# SCH_GroeiAcademie-v0_10_00_2026-07-24.net
KiCad netlist of a schematic drawn in EasyEDA
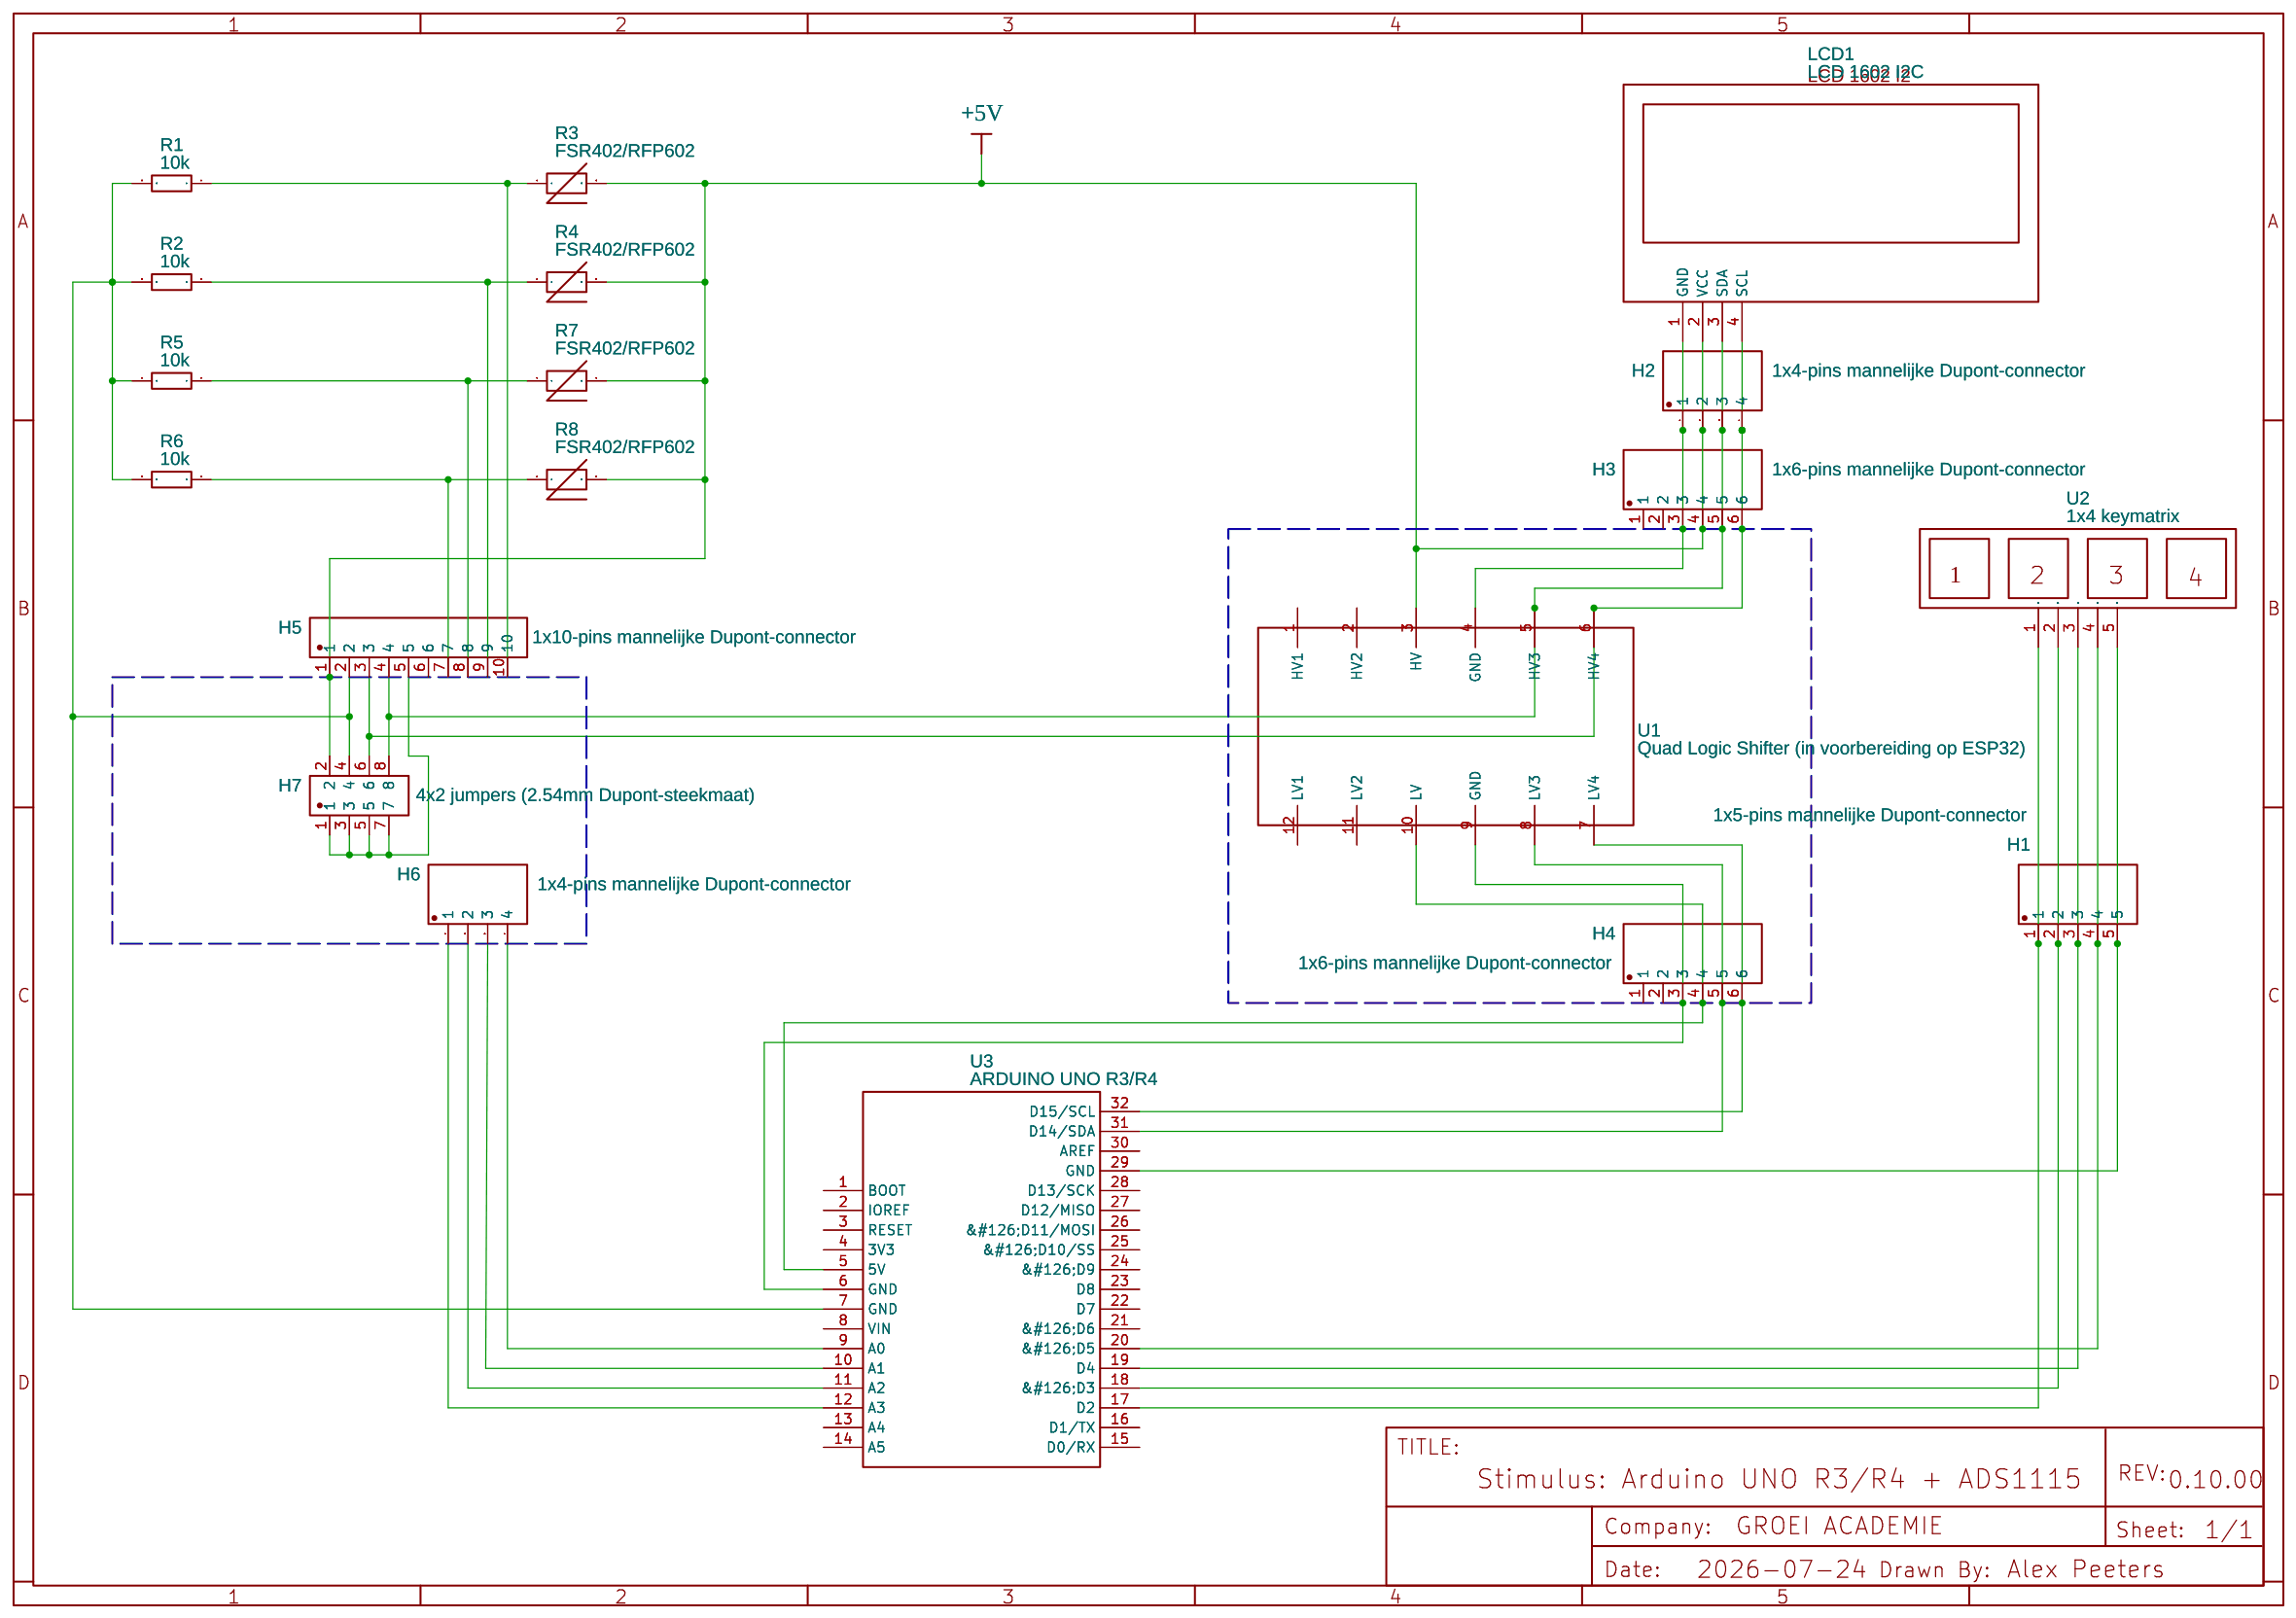
[diagram p0: schematic sheet]

(export (version "E")
  (design (tool "Eeschema 10.0.6"))
  (components
    (comp (ref "H1")
      (value "1x5-pins mannelijke Dupont-connector")
      (fields (field (name "Manufacturer Part") "B-2100S05P-A110") (field (name "Manufacturer") "Ckmtw(灿科盟)"))
      (libsource (lib "") (part "210S-1*5P L=11.6MMGold-plated black"))
    )
    (comp (ref "H2")
      (value "1x4-pins mannelijke Dupont-connector")
      (fields (field (name "Manufacturer Part") "B-2100S04P-A110") (field (name "Manufacturer") "Ckmtw(灿科盟)"))
      (libsource (lib "") (part "Header-Male-2.54_1x4"))
    )
    (comp (ref "H3")
      (value "1x6-pins mannelijke Dupont-connector")
      (fields (field (name "Manufacturer Part") "B-2100S06P-A110") (field (name "Manufacturer") "Ckmtw(灿科盟)"))
      (libsource (lib "") (part "210S-1*6P L=11.6MMGold-plated black"))
    )
    (comp (ref "H4")
      (value "1x6-pins mannelijke Dupont-connector")
      (fields (field (name "Manufacturer Part") "B-2100S06P-A110") (field (name "Manufacturer") "Ckmtw(灿科盟)"))
      (libsource (lib "") (part "210S-1*6P L=11.6MMGold-plated black"))
    )
    (comp (ref "H5")
      (value "1x10-pins mannelijke Dupont-connector")
      (fields (field (name "Manufacturer Part") "2.54-1*10") (field (name "Manufacturer") "ZHOURI(洲日)"))
      (libsource (lib "") (part "2.54-1*10"))
    )
    (comp (ref "H6")
      (value "1x4-pins mannelijke Dupont-connector")
      (fields (field (name "Manufacturer Part") "B-2100S04P-A110") (field (name "Manufacturer") "Ckmtw(灿科盟)"))
      (libsource (lib "") (part "Header-Male-2.54_1x4"))
    )
    (comp (ref "H7")
      (value "4x2 jumpers (2.54mm Dupont-steekmaat)")
      (fields (field (name "Manufacturer Part") "2.54-2*4P立贴针") (field (name "Manufacturer") "BOOMELE(博穆精密)"))
      (libsource (lib "") (part "2.54-2*4P立贴针"))
    )
    (comp (ref "LCD1") (value "LCD 1602 I2C") (libsource (lib "") (part "I2CLCD16X2_N")))
    (comp (ref "R1")
      (value "10k")
      (fields (field (name "Manufacturer") "Made in China"))
      (libsource (lib "") (part "330Ω (331) ±5%"))
    )
    (comp (ref "R2")
      (value "10k")
      (fields (field (name "Manufacturer") "Made in China"))
      (libsource (lib "") (part "330Ω (331) ±5%"))
    )
    (comp (ref "R3") (value "FSR402/RFP602") (libsource (lib "") (part "FSR402-OPCION1")))
    (comp (ref "R4") (value "FSR402/RFP602") (libsource (lib "") (part "FSR402-OPCION1")))
    (comp (ref "R5")
      (value "10k")
      (fields (field (name "Manufacturer") "Made in China"))
      (libsource (lib "") (part "330Ω (331) ±5%"))
    )
    (comp (ref "R6")
      (value "10k")
      (fields (field (name "Manufacturer") "Made in China"))
      (libsource (lib "") (part "330Ω (331) ±5%"))
    )
    (comp (ref "R7") (value "FSR402/RFP602") (libsource (lib "") (part "FSR402-OPCION1")))
    (comp (ref "R8") (value "FSR402/RFP602") (libsource (lib "") (part "FSR402-OPCION1")))
    (comp (ref "U1")
      (value "Quad Logic Shifter (in voorbereiding op ESP32)")
      (libsource (lib "") (part "Quad Logic Shifter"))
    )
    (comp (ref "U2") (value "1x4 keymatrix") (libsource (lib "") (part "Клавиатура 4*4")))
    (comp (ref "U3") (value "ARDUINO UNO R3/R4") (libsource (lib "") (part "ARDUINO UNO R4 MINIMA")))
  )
  (nets
    (net (code "1") (name "+5V") (class "Default")
      (node (ref "H2") (pin "2") (pinfunction "2_2") (pintype "unspecified"))
      (node (ref "H3") (pin "4") (pinfunction "4_4") (pintype "unspecified"))
      (node (ref "H5") (pin "1") (pinfunction "1_1") (pintype "unspecified"))
      (node (ref "H7") (pin "2") (pinfunction "2_2") (pintype "unspecified"))
      (node (ref "LCD1") (pin "2") (pinfunction "VCC_2") (pintype "unspecified"))
      (node (ref "R3") (pin "2") (pinfunction "2_2") (pintype "unspecified"))
      (node (ref "R4") (pin "2") (pinfunction "2_2") (pintype "unspecified"))
      (node (ref "R7") (pin "2") (pinfunction "2_2") (pintype "unspecified"))
      (node (ref "R8") (pin "2") (pinfunction "2_2") (pintype "unspecified"))
      (node (ref "U1") (pin "3") (pinfunction "HV_3") (pintype "unspecified"))
    )
    (net (code "2") (name "Net-(H4-Pad3)") (class "Default")
      (node (ref "H4") (pin "3") (pinfunction "3_3") (pintype "unspecified"))
      (node (ref "U1") (pin "9") (pinfunction "GND_9") (pintype "unspecified"))
      (node (ref "U3") (pin "6") (pinfunction "GND_6") (pintype "unspecified"))
    )
    (net (code "3") (name "Net-(H5-Pad2)") (class "Default")
      (node (ref "H5") (pin "2") (pinfunction "2_2") (pintype "unspecified"))
      (node (ref "H7") (pin "4") (pinfunction "4_4") (pintype "unspecified"))
      (node (ref "R1") (pin "2") (pinfunction "2_2") (pintype "unspecified"))
      (node (ref "R2") (pin "2") (pinfunction "2_2") (pintype "unspecified"))
      (node (ref "R5") (pin "2") (pinfunction "2_2") (pintype "unspecified"))
      (node (ref "R6") (pin "2") (pinfunction "2_2") (pintype "unspecified"))
      (node (ref "U3") (pin "7") (pinfunction "GND_7") (pintype "unspecified"))
    )
    (net (code "4") (name "Net-(H5-Pad5)") (class "Default")
      (node (ref "H5") (pin "5") (pinfunction "5_5") (pintype "unspecified"))
      (node (ref "H7") (pin "1") (pinfunction "1_1") (pintype "unspecified"))
      (node (ref "H7") (pin "3") (pinfunction "3_3") (pintype "unspecified"))
      (node (ref "H7") (pin "5") (pinfunction "5_5") (pintype "unspecified"))
      (node (ref "H7") (pin "7") (pinfunction "7_7") (pintype "unspecified"))
    )
    (net (code "5") (name "Net-(H5-Pad7)") (class "Default")
      (node (ref "H5") (pin "7") (pinfunction "7_7") (pintype "unspecified"))
      (node (ref "R6") (pin "1") (pinfunction "1_1") (pintype "unspecified"))
      (node (ref "R8") (pin "1") (pinfunction "1_1") (pintype "unspecified"))
    )
    (net (code "6") (name "Net-(H5-Pad8)") (class "Default")
      (node (ref "H5") (pin "8") (pinfunction "8_8") (pintype "unspecified"))
      (node (ref "R5") (pin "1") (pinfunction "1_1") (pintype "unspecified"))
      (node (ref "R7") (pin "1") (pinfunction "1_1") (pintype "unspecified"))
    )
    (net (code "7") (name "Net-(H5-Pad9)") (class "Default")
      (node (ref "H5") (pin "9") (pinfunction "9_9") (pintype "unspecified"))
      (node (ref "R2") (pin "1") (pinfunction "1_1") (pintype "unspecified"))
      (node (ref "R4") (pin "1") (pinfunction "1_1") (pintype "unspecified"))
    )
    (net (code "8") (name "Net-(H5-Pad10)") (class "Default")
      (node (ref "H5") (pin "10") (pinfunction "10_10") (pintype "unspecified"))
      (node (ref "R1") (pin "1") (pinfunction "1_1") (pintype "unspecified"))
      (node (ref "R3") (pin "1") (pinfunction "1_1") (pintype "unspecified"))
    )
    (net (code "9") (name "Net-(LCD1-GND)") (class "Default")
      (node (ref "H2") (pin "1") (pinfunction "1_1") (pintype "unspecified"))
      (node (ref "H3") (pin "3") (pinfunction "3_3") (pintype "unspecified"))
      (node (ref "LCD1") (pin "1") (pinfunction "GND_1") (pintype "unspecified"))
      (node (ref "U1") (pin "4") (pinfunction "GND_4") (pintype "unspecified"))
    )
    (net (code "10") (name "Net-(LCD1-SCL)") (class "Default")
      (node (ref "H2") (pin "4") (pinfunction "4_4") (pintype "unspecified"))
      (node (ref "H3") (pin "6") (pinfunction "6_6") (pintype "unspecified"))
      (node (ref "H5") (pin "3") (pinfunction "3_3") (pintype "unspecified"))
      (node (ref "H7") (pin "6") (pinfunction "6_6") (pintype "unspecified"))
      (node (ref "LCD1") (pin "4") (pinfunction "SCL_4") (pintype "unspecified"))
      (node (ref "U1") (pin "6") (pinfunction "HV4_6") (pintype "unspecified"))
    )
    (net (code "11") (name "Net-(LCD1-SDA)") (class "Default")
      (node (ref "H2") (pin "3") (pinfunction "3_3") (pintype "unspecified"))
      (node (ref "H3") (pin "5") (pinfunction "5_5") (pintype "unspecified"))
      (node (ref "H5") (pin "4") (pinfunction "4_4") (pintype "unspecified"))
      (node (ref "H7") (pin "8") (pinfunction "8_8") (pintype "unspecified"))
      (node (ref "LCD1") (pin "3") (pinfunction "SDA_3") (pintype "unspecified"))
      (node (ref "U1") (pin "5") (pinfunction "HV3_5") (pintype "unspecified"))
    )
    (net (code "12") (name "Net-(U1-LV)") (class "Default")
      (node (ref "H4") (pin "4") (pinfunction "4_4") (pintype "unspecified"))
      (node (ref "U1") (pin "10") (pinfunction "LV_10") (pintype "unspecified"))
      (node (ref "U3") (pin "5") (pinfunction "5V_5") (pintype "unspecified"))
    )
    (net (code "13") (name "Net-(U1-LV3)") (class "Default")
      (node (ref "H4") (pin "5") (pinfunction "5_5") (pintype "unspecified"))
      (node (ref "U1") (pin "8") (pinfunction "LV3_8") (pintype "unspecified"))
      (node (ref "U3") (pin "31") (pinfunction "D14/SDA_31") (pintype "unspecified"))
    )
    (net (code "14") (name "Net-(U1-LV4)") (class "Default")
      (node (ref "H4") (pin "6") (pinfunction "6_6") (pintype "unspecified"))
      (node (ref "U1") (pin "7") (pinfunction "LV4_7") (pintype "unspecified"))
      (node (ref "U3") (pin "32") (pinfunction "D15/SCL_32") (pintype "unspecified"))
    )
    (net (code "15") (name "Net-(U2-C1)") (class "Default")
      (node (ref "H1") (pin "1") (pinfunction "1_1") (pintype "unspecified"))
      (node (ref "U2") (pin "1") (pinfunction "C1_1") (pintype "unspecified"))
      (node (ref "U3") (pin "17") (pinfunction "D2_17") (pintype "unspecified"))
    )
    (net (code "16") (name "Net-(U2-C2)") (class "Default")
      (node (ref "H1") (pin "2") (pinfunction "2_2") (pintype "unspecified"))
      (node (ref "U2") (pin "2") (pinfunction "C2_2") (pintype "unspecified"))
      (node (ref "U3") (pin "18") (pinfunction "&#126;D3_18") (pintype "unspecified"))
    )
    (net (code "17") (name "Net-(U2-C3)") (class "Default")
      (node (ref "H1") (pin "3") (pinfunction "3_3") (pintype "unspecified"))
      (node (ref "U2") (pin "3") (pinfunction "C3_3") (pintype "unspecified"))
      (node (ref "U3") (pin "19") (pinfunction "D4_19") (pintype "unspecified"))
    )
    (net (code "18") (name "Net-(U2-R1)") (class "Default")
      (node (ref "H1") (pin "4") (pinfunction "4_4") (pintype "unspecified"))
      (node (ref "U2") (pin "4") (pinfunction "R1_4") (pintype "unspecified"))
      (node (ref "U3") (pin "20") (pinfunction "&#126;D5_20") (pintype "unspecified"))
    )
    (net (code "19") (name "Net-(U2-R2)") (class "Default")
      (node (ref "H1") (pin "5") (pinfunction "5_5") (pintype "unspecified"))
      (node (ref "U2") (pin "5") (pinfunction "R2_5") (pintype "unspecified"))
      (node (ref "U3") (pin "29") (pinfunction "GND_29") (pintype "unspecified"))
    )
    (net (code "20") (name "Net-(U3-A0)") (class "Default")
      (node (ref "H6") (pin "4") (pinfunction "4_4") (pintype "unspecified"))
      (node (ref "U3") (pin "9") (pinfunction "A0_9") (pintype "unspecified"))
    )
    (net (code "21") (name "Net-(U3-A1)") (class "Default")
      (node (ref "H6") (pin "3") (pinfunction "3_3") (pintype "unspecified"))
      (node (ref "U3") (pin "10") (pinfunction "A1_10") (pintype "unspecified"))
    )
    (net (code "22") (name "Net-(U3-A2)") (class "Default")
      (node (ref "H6") (pin "2") (pinfunction "2_2") (pintype "unspecified"))
      (node (ref "U3") (pin "11") (pinfunction "A2_11") (pintype "unspecified"))
    )
    (net (code "23") (name "Net-(U3-A3)") (class "Default")
      (node (ref "H6") (pin "1") (pinfunction "1_1") (pintype "unspecified"))
      (node (ref "U3") (pin "12") (pinfunction "A3_12") (pintype "unspecified"))
    )
    (net (code "24") (name "unconnected-(H3-Pad1)") (class "Default")
      (node (ref "H3") (pin "1") (pinfunction "1_1") (pintype "unspecified"))
    )
    (net (code "25") (name "unconnected-(H3-Pad2)") (class "Default")
      (node (ref "H3") (pin "2") (pinfunction "2_2") (pintype "unspecified"))
    )
    (net (code "26") (name "unconnected-(H4-Pad1)") (class "Default")
      (node (ref "H4") (pin "1") (pinfunction "1_1") (pintype "unspecified"))
    )
    (net (code "27") (name "unconnected-(H4-Pad2)") (class "Default")
      (node (ref "H4") (pin "2") (pinfunction "2_2") (pintype "unspecified"))
    )
    (net (code "28") (name "unconnected-(H5-Pad6)") (class "Default")
      (node (ref "H5") (pin "6") (pinfunction "6_6") (pintype "unspecified"))
    )
    (net (code "29") (name "unconnected-(U1-HV1-Pad1)") (class "Default")
      (node (ref "U1") (pin "1") (pinfunction "HV1_1") (pintype "unspecified"))
    )
    (net (code "30") (name "unconnected-(U1-HV2-Pad2)") (class "Default")
      (node (ref "U1") (pin "2") (pinfunction "HV2_2") (pintype "unspecified"))
    )
    (net (code "31") (name "unconnected-(U1-LV1-Pad12)") (class "Default")
      (node (ref "U1") (pin "12") (pinfunction "LV1_12") (pintype "unspecified"))
    )
    (net (code "32") (name "unconnected-(U1-LV2-Pad11)") (class "Default")
      (node (ref "U1") (pin "11") (pinfunction "LV2_11") (pintype "unspecified"))
    )
    (net (code "33") (name "unconnected-(U3-&#126;D6-Pad21)") (class "Default")
      (node (ref "U3") (pin "21") (pinfunction "&#126;D6_21") (pintype "unspecified"))
    )
    (net (code "34") (name "unconnected-(U3-&#126;D9-Pad24)") (class "Default")
      (node (ref "U3") (pin "24") (pinfunction "&#126;D9_24") (pintype "unspecified"))
    )
    (net (code "35") (name "unconnected-(U3-&#126;D10{slash}SS-Pad25)") (class "Default")
      (node (ref "U3") (pin "25") (pinfunction "&#126;D10/SS_25") (pintype "unspecified"))
    )
    (net (code "36") (name "unconnected-(U3-&#126;D11{slash}MOSI-Pad26)") (class "Default")
      (node (ref "U3") (pin "26") (pinfunction "&#126;D11/MOSI_26") (pintype "unspecified"))
    )
    (net (code "37") (name "unconnected-(U3-3V3-Pad4)") (class "Default")
      (node (ref "U3") (pin "4") (pinfunction "3V3_4") (pintype "unspecified"))
    )
    (net (code "38") (name "unconnected-(U3-A4-Pad13)") (class "Default")
      (node (ref "U3") (pin "13") (pinfunction "A4_13") (pintype "unspecified"))
    )
    (net (code "39") (name "unconnected-(U3-A5-Pad14)") (class "Default")
      (node (ref "U3") (pin "14") (pinfunction "A5_14") (pintype "unspecified"))
    )
    (net (code "40") (name "unconnected-(U3-AREF-Pad30)") (class "Default")
      (node (ref "U3") (pin "30") (pinfunction "AREF_30") (pintype "unspecified"))
    )
    (net (code "41") (name "unconnected-(U3-BOOT-Pad1)") (class "Default")
      (node (ref "U3") (pin "1") (pinfunction "BOOT_1") (pintype "unspecified"))
    )
    (net (code "42") (name "unconnected-(U3-D0{slash}RX-Pad15)") (class "Default")
      (node (ref "U3") (pin "15") (pinfunction "D0/RX_15") (pintype "unspecified"))
    )
    (net (code "43") (name "unconnected-(U3-D1{slash}TX-Pad16)") (class "Default")
      (node (ref "U3") (pin "16") (pinfunction "D1/TX_16") (pintype "unspecified"))
    )
    (net (code "44") (name "unconnected-(U3-D7-Pad22)") (class "Default")
      (node (ref "U3") (pin "22") (pinfunction "D7_22") (pintype "unspecified"))
    )
    (net (code "45") (name "unconnected-(U3-D8-Pad23)") (class "Default")
      (node (ref "U3") (pin "23") (pinfunction "D8_23") (pintype "unspecified"))
    )
    (net (code "46") (name "unconnected-(U3-D12{slash}MISO-Pad27)") (class "Default")
      (node (ref "U3") (pin "27") (pinfunction "D12/MISO_27") (pintype "unspecified"))
    )
    (net (code "47") (name "unconnected-(U3-D13{slash}SCK-Pad28)") (class "Default")
      (node (ref "U3") (pin "28") (pinfunction "D13/SCK_28") (pintype "unspecified"))
    )
    (net (code "48") (name "unconnected-(U3-IOREF-Pad2)") (class "Default")
      (node (ref "U3") (pin "2") (pinfunction "IOREF_2") (pintype "unspecified"))
    )
    (net (code "49") (name "unconnected-(U3-RESET-Pad3)") (class "Default")
      (node (ref "U3") (pin "3") (pinfunction "RESET_3") (pintype "unspecified"))
    )
    (net (code "50") (name "unconnected-(U3-VIN-Pad8)") (class "Default")
      (node (ref "U3") (pin "8") (pinfunction "VIN_8") (pintype "unspecified"))
    )
  )
)
